# ISP_medium_main.net
KiCad netlist of a schematic drawn in Altium Designer
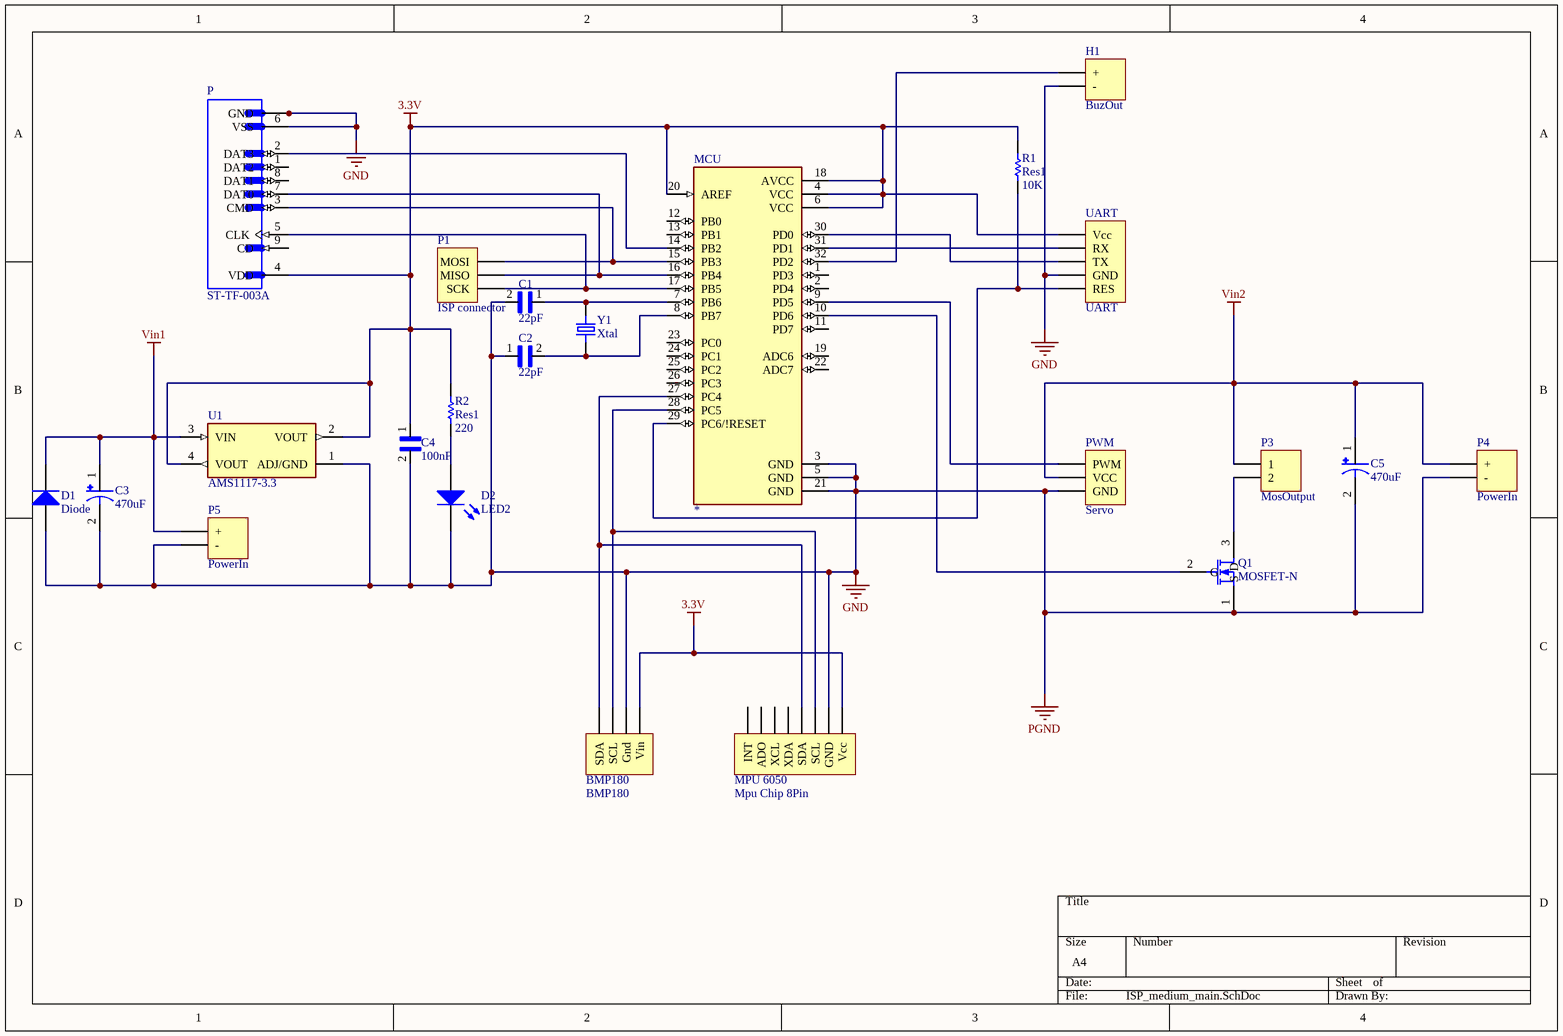
[diagram p0: ISP_medium_main.SchDoc]

(export (version "E")
  (design (tool "Eeschema 10.0.6"))
  (components
    (comp (ref "BMP180")
      (value "BMP180")
      (footprint "ISP_medium_pcb:BMP280")
      (description "Chip Connector 4 Pin for BMP180")
      (fields (field (name "PUBLISHER") "Altium Limited"))
      (libsource (lib "ISP_medium_sch") (part "BMP180"))
    )
    (comp (ref "C1")
      (value "22pF")
      (footprint "CAP1602")
      (description "SMD Capacitor X6S(EIA) with Capacitance: 22pF")
      (fields (field (name "MF") "Murata") (field (name "MP") "GRM319C81C106MA12J"))
      (libsource (lib "ISP_medium_sch") (part "22pF"))
    )
    (comp (ref "C2")
      (value "22pF")
      (footprint "CAP1602")
      (description "SMD Capacitor X6S(EIA) with Capacitance: 22pF")
      (fields (field (name "MF") "Murata") (field (name "MP") "GRM319C81C106MA12J"))
      (libsource (lib "") (part "22pF_1"))
    )
    (comp (ref "C3")
      (value "470uF")
      (footprint "CAPAE7066X77M")
      (description "470µF 16V Aluminum Electrolytic Capacitors Radial")
      (fields (field (name "MF") "Panasonic") (field (name "MP") "EEE-FC1C471AP"))
      (libsource (lib "ISP_medium_sch") (part "470uF"))
    )
    (comp (ref "C4")
      (value "100nF")
      (footprint "CAP1602")
      (description "SMD Capacitor X6S(EIA) with Capacitance: 22pF")
      (fields (field (name "MF") "Murata") (field (name "MP") "GRM319C81C106MA12J"))
      (libsource (lib "ISP_medium_sch") (part "100nF"))
    )
    (comp (ref "C5")
      (value "470uF")
      (footprint "CAPAE7066X77M")
      (description "470µF 16V Aluminum Electrolytic Capacitors Radial")
      (fields (field (name "MF") "Panasonic") (field (name "MP") "EEE-FC1C471AP"))
      (libsource (lib "ISP_medium_sch") (part "470uF"))
    )
    (comp (ref "D1")
      (value "Diode")
      (footprint "DIOM4227X24N")
      (description "Default Diode")
      (fields (field (name "PUBLISHER") "Altium Limited"))
      (libsource (lib "ISP_medium_sch") (part "Diode"))
    )
    (comp (ref "D2")
      (value "LED2")
      (footprint "3.2X1.6X1.1")
      (description "Typical RED, GREEN, YELLOW, AMBER GaAs LED")
      (fields (field (name "PUBLISHER") "Altium Limited"))
      (libsource (lib "Miscellaneous Devices") (part "LED2"))
    )
    (comp (ref "H1")
      (value "BuzOut")
      (footprint "HDR1X2")
      (description "Header, 2-Pin")
      (fields (field (name "PUBLISHER") "Altium Limited"))
      (libsource (lib "ISP_medium_sch") (part "BuzOut"))
    )
    (comp (ref "MCU")
      (value "*")
      (footprint "QFP80P900X900X120-32N")
      (description "AVR AVRÂ® ATmega Microcontroller IC 8-Bit 20MHz 32KB _16K x 16_ FLASH 32-TQFP _7x7_")
      (fields (field (name "MP") "ATMEGA328P-AU") (field (name "MF") "Microchip Technology"))
      (libsource (lib "ATMEGA328P-AU") (part "ATMEGA328P-AU"))
    )
    (comp (ref "MPU 6050")
      (value "Mpu Chip 8Pin")
      (footprint "Mpu 8Pin")
      (description "Chip Mpu 8Pin")
      (fields (field (name "PUBLISHER") "Altium Limited"))
      (libsource (lib "ISP_medium_sch") (part "Chip Mpu 8Pin"))
    )
    (comp (ref "P")
      (value "ST-TF-003A")
      (footprint "MicroSD")
      (description "Micro SD Card Socket")
      (fields (field (name "MF") "Suntech"))
      (libsource (lib "ISP_medium_sch") (part "ST-TF-003A"))
    )
    (comp (ref "P1")
      (value "ISP connector")
      (footprint "ISP connector")
      (description "Header, 3-Pin")
      (fields (field (name "PUBLISHER") "Altium Limited"))
      (libsource (lib "ISP_medium_sch") (part "ISP connector"))
    )
    (comp (ref "P3")
      (value "MosOutput")
      (footprint "HDR1X2")
      (description "Header, 2-Pin")
      (fields (field (name "PUBLISHER") "Altium Limited"))
      (libsource (lib "ISP_medium_sch") (part "MosOutput"))
    )
    (comp (ref "P4")
      (value "PowerIn")
      (footprint "PowerIn")
      (description "Header, 2-Pin")
      (fields (field (name "PUBLISHER") "Altium Limited"))
      (libsource (lib "ISP_medium_sch") (part "PowerIn"))
    )
    (comp (ref "P5")
      (value "PowerIn")
      (footprint "PowerIn")
      (description "Header, 2-Pin")
      (fields (field (name "PUBLISHER") "Altium Limited"))
      (libsource (lib "ISP_medium_sch") (part "PowerIn"))
    )
    (comp (ref "PWM")
      (value "Servo")
      (footprint "Servo")
      (description "Header, 3-Pin")
      (fields (field (name "PUBLISHER") "Altium Limited"))
      (libsource (lib "ISP_medium_sch") (part "Servo"))
    )
    (comp (ref "Q1")
      (value "MOSFET-N")
      (footprint "SOT23-3")
      (description "N-Channel MOSFET")
      (fields (field (name "PUBLISHER") "Altium Limited"))
      (libsource (lib "ISP_medium_sch") (part "MOSFET-N"))
    )
    (comp (ref "R1")
      (value "Res1")
      (footprint "RES 1602")
      (description "Resistor")
      (fields (field (name "ALTIUM_VALUE") "10K") (field (name "PUBLISHER") "Altium Limited"))
      (libsource (lib "ISP_medium_sch") (part "Res1"))
    )
    (comp (ref "R2")
      (value "Res1")
      (footprint "RES 1602")
      (description "Resistor")
      (fields (field (name "ALTIUM_VALUE") "220") (field (name "PUBLISHER") "Altium Limited"))
      (libsource (lib "ISP_medium_sch") (part "Res1"))
    )
    (comp (ref "U1")
      (value "AMS1117-3.3")
      (footprint "SOT230P700X180-4N")
      (description "Sot223/Pkg 1-Amp 3.3-Volt Low Drop Out Voltage Regulatator")
      (fields (field (name "MF") "Advanced Monolithic Systems"))
      (libsource (lib "ISP_medium_sch") (part "AMS1117-3.3"))
    )
    (comp (ref "UART")
      (value "UART")
      (footprint "UART")
      (description "Header, 5-Pin, UART, for uploading")
      (fields (field (name "PUBLISHER") "Altium Limited"))
      (libsource (lib "ISP_medium_sch") (part "UART"))
    )
    (comp (ref "Y1")
      (value "Xtal")
      (footprint "XTAL")
      (fields (field (name "MP") "ECS-122.8-18-5PXEN-TR") (field (name "MF") "ECS Inc."))
      (libsource (lib "ISP_medium_sch") (part "Xtal"))
    )
  )
  (nets
    (net (code "1") (name "3.3V") (class "Default")
      (node (ref "BMP180") (pin "1") (pinfunction "Vin_1") (pintype "passive"))
      (node (ref "C4") (pin "1") (pinfunction "1_1") (pintype "passive"))
      (node (ref "MCU") (pin "18") (pinfunction "AVCC_18") (pintype "power_in"))
      (node (ref "MCU") (pin "20") (pinfunction "AREF_20") (pintype "input"))
      (node (ref "MCU") (pin "4") (pinfunction "VCC_4") (pintype "power_in"))
      (node (ref "MCU") (pin "6") (pinfunction "VCC_6") (pintype "power_in"))
      (node (ref "MPU 6050") (pin "1") (pinfunction "Vcc_1") (pintype "passive"))
      (node (ref "P") (pin "4") (pinfunction "VDD_4") (pintype "power_in"))
      (node (ref "R1") (pin "2") (pinfunction "2_2") (pintype "passive"))
      (node (ref "R2") (pin "2") (pinfunction "2_2") (pintype "passive"))
      (node (ref "U1") (pin "2") (pinfunction "VOUT_2") (pintype "output"))
      (node (ref "U1") (pin "4") (pinfunction "VOUT_4") (pintype "output"))
      (node (ref "UART") (pin "1") (pinfunction "Vcc_1") (pintype "passive"))
    )
    (net (code "2") (name "GND") (class "Default")
      (node (ref "BMP180") (pin "2") (pinfunction "Gnd_2") (pintype "passive"))
      (node (ref "C1") (pin "2") (pinfunction "2_2") (pintype "passive"))
      (node (ref "C2") (pin "1") (pinfunction "1_1") (pintype "passive"))
      (node (ref "C3") (pin "2") (pinfunction "-_2") (pintype "passive"))
      (node (ref "C4") (pin "2") (pinfunction "2_2") (pintype "passive"))
      (node (ref "C5") (pin "2") (pinfunction "-_2") (pintype "passive"))
      (node (ref "D1") (pin "1") (pinfunction "A_1") (pintype "passive"))
      (node (ref "D2") (pin "2") (pinfunction "K_2") (pintype "passive"))
      (node (ref "H1") (pin "2") (pinfunction "-_2") (pintype "passive"))
      (node (ref "MCU") (pin "21") (pinfunction "GND_21") (pintype "power_in"))
      (node (ref "MCU") (pin "3") (pinfunction "GND_3") (pintype "power_in"))
      (node (ref "MCU") (pin "5") (pinfunction "GND_5") (pintype "power_in"))
      (node (ref "MPU 6050") (pin "2") (pinfunction "GND_2") (pintype "passive"))
      (node (ref "P") (pin "6") (pinfunction "VSS_6") (pintype "passive"))
      (node (ref "P") (pin "G1") (pinfunction "GND_G1") (pintype "passive"))
      (node (ref "P") (pin "G2") (pinfunction "GND_G2") (pintype "passive"))
      (node (ref "P") (pin "G3") (pinfunction "GND_G3") (pintype "passive"))
      (node (ref "P") (pin "G4") (pinfunction "GND_G4") (pintype "passive"))
      (node (ref "P4") (pin "2") (pinfunction "-_2") (pintype "passive"))
      (node (ref "P5") (pin "2") (pinfunction "-_2") (pintype "passive"))
      (node (ref "PWM") (pin "3") (pinfunction "GND_3") (pintype "passive"))
      (node (ref "Q1") (pin "1") (pinfunction "S_1") (pintype "passive"))
      (node (ref "U1") (pin "1") (pinfunction "ADJ/GND_1") (pintype "power_in"))
      (node (ref "UART") (pin "4") (pinfunction "GND_4") (pintype "passive"))
    )
    (net (code "3") (name "Net-(BMP180-SCL)") (class "Default")
      (node (ref "BMP180") (pin "3") (pinfunction "SCL_3") (pintype "passive"))
      (node (ref "MCU") (pin "28") (pinfunction "PC5_28") (pintype "bidirectional"))
      (node (ref "MPU 6050") (pin "3") (pinfunction "SCL_3") (pintype "passive"))
    )
    (net (code "4") (name "Net-(BMP180-SDA)") (class "Default")
      (node (ref "BMP180") (pin "4") (pinfunction "SDA_4") (pintype "passive"))
      (node (ref "MCU") (pin "27") (pinfunction "PC4_27") (pintype "bidirectional"))
      (node (ref "MPU 6050") (pin "4") (pinfunction "SDA_4") (pintype "passive"))
    )
    (net (code "5") (name "Net-(D2-A)") (class "Default")
      (node (ref "D2") (pin "1") (pinfunction "A_1") (pintype "passive"))
      (node (ref "R2") (pin "1") (pinfunction "1_1") (pintype "passive"))
    )
    (net (code "6") (name "Net-(H1-+)") (class "Default")
      (node (ref "H1") (pin "1") (pinfunction "+_1") (pintype "passive"))
      (node (ref "MCU") (pin "32") (pinfunction "PD2_32") (pintype "bidirectional"))
    )
    (net (code "7") (name "Net-(MCU-PB2)") (class "Default")
      (node (ref "MCU") (pin "14") (pinfunction "PB2_14") (pintype "bidirectional"))
      (node (ref "P") (pin "2") (pinfunction "DAT3_2") (pintype "bidirectional"))
    )
    (net (code "8") (name "Net-(MCU-PB3)") (class "Default")
      (node (ref "MCU") (pin "15") (pinfunction "PB3_15") (pintype "bidirectional"))
      (node (ref "P") (pin "3") (pinfunction "CMD_3") (pintype "bidirectional"))
      (node (ref "P1") (pin "3") (pinfunction "MOSI_3") (pintype "passive"))
    )
    (net (code "9") (name "Net-(MCU-PB4)") (class "Default")
      (node (ref "MCU") (pin "16") (pinfunction "PB4_16") (pintype "bidirectional"))
      (node (ref "P") (pin "7") (pinfunction "DAT0_7") (pintype "bidirectional"))
      (node (ref "P1") (pin "2") (pinfunction "MISO_2") (pintype "passive"))
    )
    (net (code "10") (name "Net-(MCU-PB5)") (class "Default")
      (node (ref "MCU") (pin "17") (pinfunction "PB5_17") (pintype "bidirectional"))
      (node (ref "P") (pin "5") (pinfunction "CLK_5") (pintype "input"))
      (node (ref "P1") (pin "1") (pinfunction "SCK_1") (pintype "passive"))
    )
    (net (code "11") (name "Net-(MCU-PB6)") (class "Default")
      (node (ref "C1") (pin "1") (pinfunction "1_1") (pintype "passive"))
      (node (ref "MCU") (pin "7") (pinfunction "PB6_7") (pintype "bidirectional"))
      (node (ref "Y1") (pin "2") (pinfunction "2_2") (pintype "passive"))
    )
    (net (code "12") (name "Net-(MCU-PB7)") (class "Default")
      (node (ref "C2") (pin "2") (pinfunction "2_2") (pintype "passive"))
      (node (ref "MCU") (pin "8") (pinfunction "PB7_8") (pintype "bidirectional"))
      (node (ref "Y1") (pin "1") (pinfunction "1_1") (pintype "passive"))
    )
    (net (code "13") (name "Net-(MCU-PC6{slash}!RESET)") (class "Default")
      (node (ref "MCU") (pin "29") (pinfunction "PC6/!RESET_29") (pintype "bidirectional"))
      (node (ref "R1") (pin "1") (pinfunction "1_1") (pintype "passive"))
      (node (ref "UART") (pin "5") (pinfunction "RES_5") (pintype "passive"))
    )
    (net (code "14") (name "Net-(MCU-PD0)") (class "Default")
      (node (ref "MCU") (pin "30") (pinfunction "PD0_30") (pintype "bidirectional"))
      (node (ref "UART") (pin "3") (pinfunction "TX_3") (pintype "passive"))
    )
    (net (code "15") (name "Net-(MCU-PD1)") (class "Default")
      (node (ref "MCU") (pin "31") (pinfunction "PD1_31") (pintype "bidirectional"))
      (node (ref "UART") (pin "2") (pinfunction "RX_2") (pintype "passive"))
    )
    (net (code "16") (name "Net-(MCU-PD5)") (class "Default")
      (node (ref "MCU") (pin "9") (pinfunction "PD5_9") (pintype "bidirectional"))
      (node (ref "PWM") (pin "1") (pinfunction "PWM_1") (pintype "passive"))
    )
    (net (code "17") (name "Net-(MCU-PD6)") (class "Default")
      (node (ref "MCU") (pin "10") (pinfunction "PD6_10") (pintype "bidirectional"))
      (node (ref "Q1") (pin "2") (pinfunction "G_2") (pintype "passive"))
    )
    (net (code "18") (name "Net-(Q1-D)") (class "Default")
      (node (ref "P3") (pin "2") (pinfunction "2_2") (pintype "passive"))
      (node (ref "Q1") (pin "3") (pinfunction "D_3") (pintype "passive"))
    )
    (net (code "19") (name "Vin1") (class "Default")
      (node (ref "C3") (pin "1") (pinfunction "+_1") (pintype "passive"))
      (node (ref "D1") (pin "2") (pinfunction "K_2") (pintype "passive"))
      (node (ref "P5") (pin "1") (pinfunction "+_1") (pintype "passive"))
      (node (ref "U1") (pin "3") (pinfunction "VIN_3") (pintype "input"))
    )
    (net (code "20") (name "Vin2") (class "Default")
      (node (ref "C5") (pin "1") (pinfunction "+_1") (pintype "passive"))
      (node (ref "P3") (pin "1") (pinfunction "1_1") (pintype "passive"))
      (node (ref "P4") (pin "1") (pinfunction "+_1") (pintype "passive"))
      (node (ref "PWM") (pin "2") (pinfunction "VCC_2") (pintype "passive"))
    )
    (net (code "21") (name "unconnected-(MCU-ADC6-Pad19)") (class "Default")
      (node (ref "MCU") (pin "19") (pinfunction "ADC6_19") (pintype "bidirectional"))
    )
    (net (code "22") (name "unconnected-(MCU-ADC7-Pad22)") (class "Default")
      (node (ref "MCU") (pin "22") (pinfunction "ADC7_22") (pintype "bidirectional"))
    )
    (net (code "23") (name "unconnected-(MCU-PB0-Pad12)") (class "Default")
      (node (ref "MCU") (pin "12") (pinfunction "PB0_12") (pintype "bidirectional"))
    )
    (net (code "24") (name "unconnected-(MCU-PB1-Pad13)") (class "Default")
      (node (ref "MCU") (pin "13") (pinfunction "PB1_13") (pintype "bidirectional"))
    )
    (net (code "25") (name "unconnected-(MCU-PC0-Pad23)") (class "Default")
      (node (ref "MCU") (pin "23") (pinfunction "PC0_23") (pintype "bidirectional"))
    )
    (net (code "26") (name "unconnected-(MCU-PC1-Pad24)") (class "Default")
      (node (ref "MCU") (pin "24") (pinfunction "PC1_24") (pintype "bidirectional"))
    )
    (net (code "27") (name "unconnected-(MCU-PC2-Pad25)") (class "Default")
      (node (ref "MCU") (pin "25") (pinfunction "PC2_25") (pintype "bidirectional"))
    )
    (net (code "28") (name "unconnected-(MCU-PC3-Pad26)") (class "Default")
      (node (ref "MCU") (pin "26") (pinfunction "PC3_26") (pintype "bidirectional"))
    )
    (net (code "29") (name "unconnected-(MCU-PD3-Pad1)") (class "Default")
      (node (ref "MCU") (pin "1") (pinfunction "PD3_1") (pintype "bidirectional"))
    )
    (net (code "30") (name "unconnected-(MCU-PD4-Pad2)") (class "Default")
      (node (ref "MCU") (pin "2") (pinfunction "PD4_2") (pintype "bidirectional"))
    )
    (net (code "31") (name "unconnected-(MCU-PD7-Pad11)") (class "Default")
      (node (ref "MCU") (pin "11") (pinfunction "PD7_11") (pintype "bidirectional"))
    )
    (net (code "32") (name "unconnected-(MPU 6050-ADO-Pad7)") (class "Default")
      (node (ref "MPU 6050") (pin "7") (pinfunction "ADO_7") (pintype "passive"))
    )
    (net (code "33") (name "unconnected-(MPU 6050-INT-Pad8)") (class "Default")
      (node (ref "MPU 6050") (pin "8") (pinfunction "INT_8") (pintype "passive"))
    )
    (net (code "34") (name "unconnected-(MPU 6050-XCL-Pad6)") (class "Default")
      (node (ref "MPU 6050") (pin "6") (pinfunction "XCL_6") (pintype "passive"))
    )
    (net (code "35") (name "unconnected-(MPU 6050-XDA-Pad5)") (class "Default")
      (node (ref "MPU 6050") (pin "5") (pinfunction "XDA_5") (pintype "passive"))
    )
    (net (code "36") (name "unconnected-(P-CD-Pad9)") (class "Default")
      (node (ref "P") (pin "9") (pinfunction "CD_9") (pintype "input"))
    )
    (net (code "37") (name "unconnected-(P-DAT1-Pad8)") (class "Default")
      (node (ref "P") (pin "8") (pinfunction "DAT1_8") (pintype "bidirectional"))
    )
    (net (code "38") (name "unconnected-(P-DAT2-Pad1)") (class "Default")
      (node (ref "P") (pin "1") (pinfunction "DAT2_1") (pintype "bidirectional"))
    )
  )
)
